# adruino_robot_rev.net
KiCad netlist of a schematic drawn in EAGLE
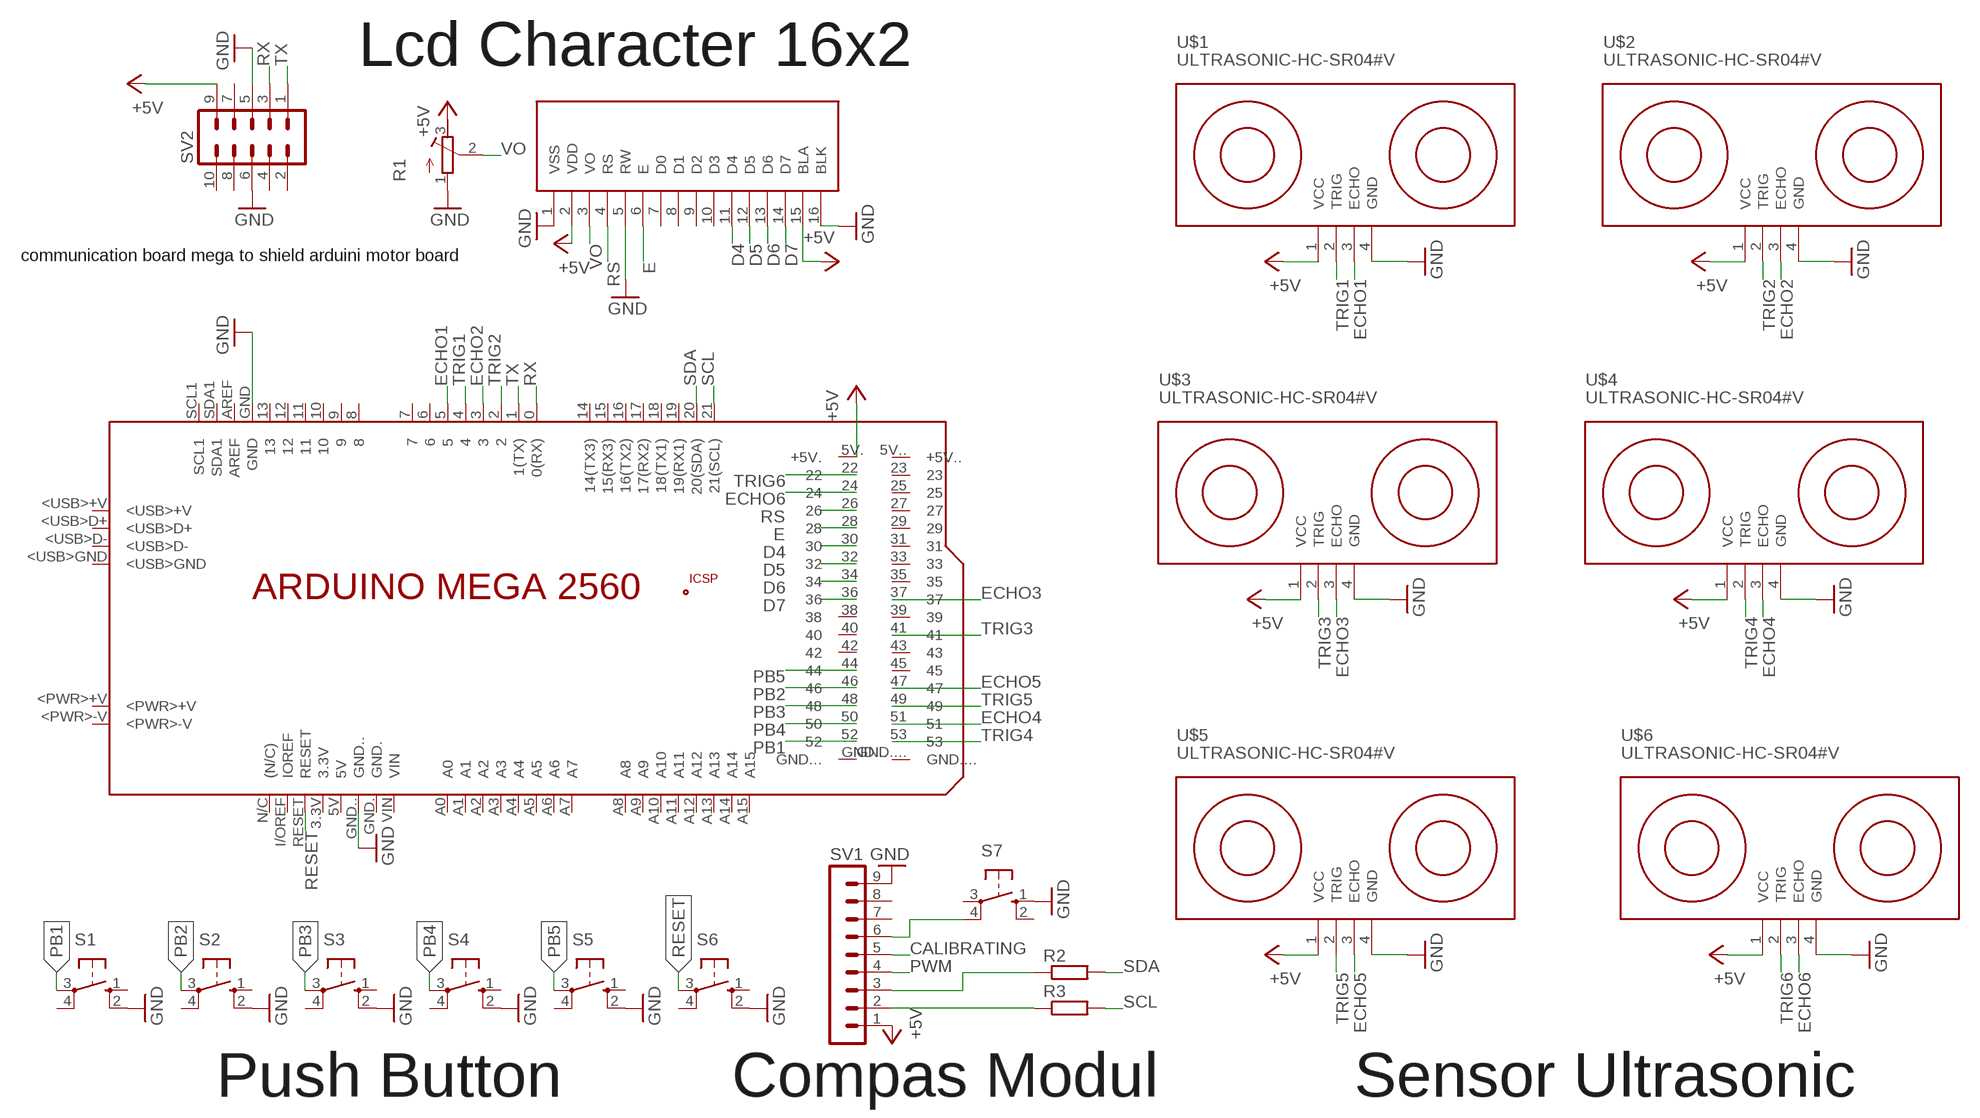
[diagram p0: schematic, sheet 1]

(export (version "E")
  (design (tool "Eeschema 10.0.6"))
  (components
    (comp (ref "PCB1")
      (value "ARDUINO_MEGA2560")
      (footprint "eagle-import:ARDUINO_MEGA2560")
      (libsource (lib "eagle-import") (part "ARDUINO_MEGA2560"))
    )
    (comp (ref "R1")
      (value "R-TRIMM3339P")
      (footprint "eagle-import:RTRIM3339P")
      (libsource (lib "eagle-import") (part "R-TRIMM3339P"))
    )
    (comp (ref "R2")
      (value "R-EU_0204/7")
      (footprint "eagle-import:0204_7")
      (libsource (lib "eagle-import") (part "R-EU_0204/7"))
    )
    (comp (ref "R3")
      (value "R-EU_0204/7")
      (footprint "eagle-import:0204_7")
      (libsource (lib "eagle-import") (part "R-EU_0204/7"))
    )
    (comp (ref "S1")
      (value "40-XX")
      (footprint "eagle-import:B3F-40XX")
      (fields (field (name "MF") "OMRON COMPONENTS USA") (field (name "MPN") "B3F-4000"))
      (libsource (lib "eagle-import") (part "40-XX"))
    )
    (comp (ref "S2")
      (value "40-XX")
      (footprint "eagle-import:B3F-40XX")
      (fields (field (name "MF") "OMRON COMPONENTS USA") (field (name "MPN") "B3F-4000"))
      (libsource (lib "eagle-import") (part "40-XX"))
    )
    (comp (ref "S3")
      (value "40-XX")
      (footprint "eagle-import:B3F-40XX")
      (fields (field (name "MF") "OMRON COMPONENTS USA") (field (name "MPN") "B3F-4000"))
      (libsource (lib "eagle-import") (part "40-XX"))
    )
    (comp (ref "S4")
      (value "40-XX")
      (footprint "eagle-import:B3F-40XX")
      (fields (field (name "MF") "OMRON COMPONENTS USA") (field (name "MPN") "B3F-4000"))
      (libsource (lib "eagle-import") (part "40-XX"))
    )
    (comp (ref "S5")
      (value "40-XX")
      (footprint "eagle-import:B3F-40XX")
      (fields (field (name "MF") "OMRON COMPONENTS USA") (field (name "MPN") "B3F-4000"))
      (libsource (lib "eagle-import") (part "40-XX"))
    )
    (comp (ref "S6")
      (value "40-XX")
      (footprint "eagle-import:B3F-40XX")
      (fields (field (name "MF") "OMRON COMPONENTS USA") (field (name "MPN") "B3F-4000"))
      (libsource (lib "eagle-import") (part "40-XX"))
    )
    (comp (ref "S7")
      (value "40-XX")
      (footprint "eagle-import:B3F-40XX")
      (fields (field (name "MF") "OMRON COMPONENTS USA") (field (name "MPN") "B3F-4000"))
      (libsource (lib "eagle-import") (part "40-XX"))
    )
    (comp (ref "SV1")
      (value "MA09-1")
      (footprint "eagle-import:MA09-1")
      (libsource (lib "eagle-import") (part "MA09-1"))
    )
    (comp (ref "SV2")
      (value "ML10")
      (footprint "eagle-import:ML10")
      (libsource (lib "eagle-import") (part "ML10"))
    )
    (comp (ref "U$1")
      (value "ULTRASONIC-HC-SR04#V")
      (footprint "eagle-import:ULTRASONIC-HC-SR04#V")
      (libsource (lib "eagle-import") (part "ULTRASONIC-HC-SR04#V"))
    )
    (comp (ref "U$2")
      (value "ULTRASONIC-HC-SR04#V")
      (footprint "eagle-import:ULTRASONIC-HC-SR04#V")
      (libsource (lib "eagle-import") (part "ULTRASONIC-HC-SR04#V"))
    )
    (comp (ref "U$3")
      (value "ULTRASONIC-HC-SR04#V")
      (footprint "eagle-import:ULTRASONIC-HC-SR04#V")
      (libsource (lib "eagle-import") (part "ULTRASONIC-HC-SR04#V"))
    )
    (comp (ref "U$4")
      (value "ULTRASONIC-HC-SR04#V")
      (footprint "eagle-import:ULTRASONIC-HC-SR04#V")
      (libsource (lib "eagle-import") (part "ULTRASONIC-HC-SR04#V"))
    )
    (comp (ref "U$5")
      (value "ULTRASONIC-HC-SR04#V")
      (footprint "eagle-import:ULTRASONIC-HC-SR04#V")
      (libsource (lib "eagle-import") (part "ULTRASONIC-HC-SR04#V"))
    )
    (comp (ref "U$6")
      (value "ULTRASONIC-HC-SR04#V")
      (footprint "eagle-import:ULTRASONIC-HC-SR04#V")
      (libsource (lib "eagle-import") (part "ULTRASONIC-HC-SR04#V"))
    )
    (comp (ref "U$7")
      (value "2X16LCDTOP")
      (footprint "eagle-import:2X16LCDTOP")
      (libsource (lib "eagle-import") (part "2X16LCDTOP"))
    )
  )
  (nets
    (net (code "1") (name "+5V") (class "Default")
      (node (ref "PCB1") (pin "5V.") (pinfunction "+5V._5V.") (pintype "bidirectional"))
      (node (ref "R1") (pin "3") (pinfunction "E_3") (pintype "passive"))
      (node (ref "SV1") (pin "1") (pinfunction "1_1") (pintype "passive"))
      (node (ref "SV2") (pin "9") (pinfunction "9_9") (pintype "passive"))
      (node (ref "U$1") (pin "1") (pinfunction "VCC_1") (pintype "power_in"))
      (node (ref "U$2") (pin "1") (pinfunction "VCC_1") (pintype "power_in"))
      (node (ref "U$3") (pin "1") (pinfunction "VCC_1") (pintype "power_in"))
      (node (ref "U$4") (pin "1") (pinfunction "VCC_1") (pintype "power_in"))
      (node (ref "U$5") (pin "1") (pinfunction "VCC_1") (pintype "power_in"))
      (node (ref "U$6") (pin "1") (pinfunction "VCC_1") (pintype "power_in"))
      (node (ref "U$7") (pin "15") (pinfunction "BLA_15") (pintype "bidirectional"))
      (node (ref "U$7") (pin "2") (pinfunction "VDD_2") (pintype "bidirectional"))
    )
    (net (code "2") (name "/CALIBRATING") (class "Default")
      (node (ref "SV1") (pin "5") (pinfunction "5_5") (pintype "passive"))
    )
    (net (code "3") (name "/D4") (class "Default")
      (node (ref "PCB1") (pin "30") (pinfunction "30_30") (pintype "bidirectional"))
      (node (ref "U$7") (pin "11") (pinfunction "D4_11") (pintype "bidirectional"))
    )
    (net (code "4") (name "/D5") (class "Default")
      (node (ref "PCB1") (pin "32") (pinfunction "32_32") (pintype "bidirectional"))
      (node (ref "U$7") (pin "12") (pinfunction "D5_12") (pintype "bidirectional"))
    )
    (net (code "5") (name "/D6") (class "Default")
      (node (ref "PCB1") (pin "34") (pinfunction "34_34") (pintype "bidirectional"))
      (node (ref "U$7") (pin "13") (pinfunction "D6_13") (pintype "bidirectional"))
    )
    (net (code "6") (name "/D7") (class "Default")
      (node (ref "PCB1") (pin "36") (pinfunction "36_36") (pintype "bidirectional"))
      (node (ref "U$7") (pin "14") (pinfunction "D7_14") (pintype "bidirectional"))
    )
    (net (code "7") (name "/E") (class "Default")
      (node (ref "PCB1") (pin "28") (pinfunction "28_28") (pintype "bidirectional"))
      (node (ref "U$7") (pin "6") (pinfunction "E_6") (pintype "bidirectional"))
    )
    (net (code "8") (name "/ECHO1") (class "Default")
      (node (ref "PCB1") (pin "5") (pinfunction "5_5") (pintype "bidirectional"))
      (node (ref "U$1") (pin "3") (pinfunction "ECHO_3") (pintype "output"))
    )
    (net (code "9") (name "/ECHO2") (class "Default")
      (node (ref "PCB1") (pin "3") (pinfunction "3_3") (pintype "bidirectional"))
      (node (ref "U$2") (pin "3") (pinfunction "ECHO_3") (pintype "output"))
    )
    (net (code "10") (name "/ECHO3") (class "Default")
      (node (ref "PCB1") (pin "37") (pinfunction "37_37") (pintype "bidirectional"))
      (node (ref "U$3") (pin "3") (pinfunction "ECHO_3") (pintype "output"))
    )
    (net (code "11") (name "/ECHO4") (class "Default")
      (node (ref "PCB1") (pin "51") (pinfunction "51_51") (pintype "bidirectional"))
      (node (ref "U$4") (pin "3") (pinfunction "ECHO_3") (pintype "output"))
    )
    (net (code "12") (name "/ECHO5") (class "Default")
      (node (ref "PCB1") (pin "47") (pinfunction "47_47") (pintype "bidirectional"))
      (node (ref "U$5") (pin "3") (pinfunction "ECHO_3") (pintype "output"))
    )
    (net (code "13") (name "/ECHO6") (class "Default")
      (node (ref "PCB1") (pin "24") (pinfunction "24_24") (pintype "bidirectional"))
      (node (ref "U$6") (pin "3") (pinfunction "ECHO_3") (pintype "output"))
    )
    (net (code "14") (name "/PWM") (class "Default")
      (node (ref "SV1") (pin "4") (pinfunction "4_4") (pintype "passive"))
    )
    (net (code "15") (name "/RS") (class "Default")
      (node (ref "PCB1") (pin "26") (pinfunction "26_26") (pintype "bidirectional"))
      (node (ref "U$7") (pin "4") (pinfunction "RS_4") (pintype "bidirectional"))
    )
    (net (code "16") (name "/RX") (class "Default")
      (node (ref "PCB1") (pin "0") (pinfunction "0(RX)_0") (pintype "bidirectional"))
      (node (ref "SV2") (pin "3") (pinfunction "3_3") (pintype "passive"))
    )
    (net (code "17") (name "/SCL") (class "Default")
      (node (ref "PCB1") (pin "21") (pinfunction "21(SCL)_21") (pintype "bidirectional"))
      (node (ref "R3") (pin "2") (pinfunction "2_2") (pintype "passive"))
    )
    (net (code "18") (name "/SDA") (class "Default")
      (node (ref "PCB1") (pin "20") (pinfunction "20(SDA)_20") (pintype "bidirectional"))
      (node (ref "R2") (pin "2") (pinfunction "2_2") (pintype "passive"))
    )
    (net (code "19") (name "/TRIG1") (class "Default")
      (node (ref "PCB1") (pin "4") (pinfunction "4_4") (pintype "bidirectional"))
      (node (ref "U$1") (pin "2") (pinfunction "TRIG_2") (pintype "input"))
    )
    (net (code "20") (name "/TRIG2") (class "Default")
      (node (ref "PCB1") (pin "2") (pinfunction "2_2") (pintype "bidirectional"))
      (node (ref "U$2") (pin "2") (pinfunction "TRIG_2") (pintype "input"))
    )
    (net (code "21") (name "/TRIG3") (class "Default")
      (node (ref "PCB1") (pin "41") (pinfunction "41_41") (pintype "bidirectional"))
      (node (ref "U$3") (pin "2") (pinfunction "TRIG_2") (pintype "input"))
    )
    (net (code "22") (name "/TRIG4") (class "Default")
      (node (ref "PCB1") (pin "53") (pinfunction "53_53") (pintype "bidirectional"))
      (node (ref "U$4") (pin "2") (pinfunction "TRIG_2") (pintype "input"))
    )
    (net (code "23") (name "/TRIG5") (class "Default")
      (node (ref "PCB1") (pin "49") (pinfunction "49_49") (pintype "bidirectional"))
      (node (ref "U$5") (pin "2") (pinfunction "TRIG_2") (pintype "input"))
    )
    (net (code "24") (name "/TRIG6") (class "Default")
      (node (ref "PCB1") (pin "22") (pinfunction "22_22") (pintype "bidirectional"))
      (node (ref "U$6") (pin "2") (pinfunction "TRIG_2") (pintype "input"))
    )
    (net (code "25") (name "/TX") (class "Default")
      (node (ref "PCB1") (pin "1") (pinfunction "1(TX)_1") (pintype "bidirectional"))
      (node (ref "SV2") (pin "1") (pinfunction "1_1") (pintype "passive"))
    )
    (net (code "26") (name "/VO") (class "Default")
      (node (ref "R1") (pin "2") (pinfunction "S_2") (pintype "passive"))
      (node (ref "U$7") (pin "3") (pinfunction "VO_3") (pintype "bidirectional"))
    )
    (net (code "27") (name "GND") (class "Default")
      (node (ref "PCB1") (pin "GND") (pinfunction "GND_GND") (pintype "bidirectional"))
      (node (ref "PCB1") (pin "GND..") (pinfunction "GND.._GND..") (pintype "bidirectional"))
      (node (ref "R1") (pin "1") (pinfunction "A_1") (pintype "passive"))
      (node (ref "S1") (pin "2") (pinfunction "S1_2") (pintype "passive"))
      (node (ref "S2") (pin "2") (pinfunction "S1_2") (pintype "passive"))
      (node (ref "S3") (pin "2") (pinfunction "S1_2") (pintype "passive"))
      (node (ref "S4") (pin "2") (pinfunction "S1_2") (pintype "passive"))
      (node (ref "S5") (pin "2") (pinfunction "S1_2") (pintype "passive"))
      (node (ref "S6") (pin "2") (pinfunction "S1_2") (pintype "passive"))
      (node (ref "S7") (pin "1") (pinfunction "S_1") (pintype "passive"))
      (node (ref "SV1") (pin "9") (pinfunction "9_9") (pintype "passive"))
      (node (ref "SV2") (pin "5") (pinfunction "5_5") (pintype "passive"))
      (node (ref "SV2") (pin "6") (pinfunction "6_6") (pintype "passive"))
      (node (ref "U$1") (pin "4") (pinfunction "GND_4") (pintype "power_in"))
      (node (ref "U$2") (pin "4") (pinfunction "GND_4") (pintype "power_in"))
      (node (ref "U$3") (pin "4") (pinfunction "GND_4") (pintype "power_in"))
      (node (ref "U$4") (pin "4") (pinfunction "GND_4") (pintype "power_in"))
      (node (ref "U$5") (pin "4") (pinfunction "GND_4") (pintype "power_in"))
      (node (ref "U$6") (pin "4") (pinfunction "GND_4") (pintype "power_in"))
      (node (ref "U$7") (pin "1") (pinfunction "VSS_1") (pintype "bidirectional"))
      (node (ref "U$7") (pin "16") (pinfunction "BLK_16") (pintype "bidirectional"))
      (node (ref "U$7") (pin "5") (pinfunction "RW_5") (pintype "bidirectional"))
    )
    (net (code "28") (name "Net-(R2-Pad1)") (class "Default")
      (node (ref "R2") (pin "1") (pinfunction "1_1") (pintype "passive"))
      (node (ref "SV1") (pin "3") (pinfunction "3_3") (pintype "passive"))
    )
    (net (code "29") (name "Net-(R3-Pad1)") (class "Default")
      (node (ref "R3") (pin "1") (pinfunction "1_1") (pintype "passive"))
      (node (ref "SV1") (pin "2") (pinfunction "2_2") (pintype "passive"))
    )
    (net (code "30") (name "Net-(S7-P1)") (class "Default")
      (node (ref "S7") (pin "4") (pinfunction "P1_4") (pintype "passive"))
      (node (ref "SV1") (pin "6") (pinfunction "6_6") (pintype "passive"))
    )
    (net (code "31") (name "PB1") (class "Default")
      (node (ref "PCB1") (pin "52") (pinfunction "52_52") (pintype "bidirectional"))
      (node (ref "S1") (pin "3") (pinfunction "P_3") (pintype "passive"))
    )
    (net (code "32") (name "PB2") (class "Default")
      (node (ref "PCB1") (pin "46") (pinfunction "46_46") (pintype "bidirectional"))
      (node (ref "S2") (pin "3") (pinfunction "P_3") (pintype "passive"))
    )
    (net (code "33") (name "PB3") (class "Default")
      (node (ref "PCB1") (pin "48") (pinfunction "48_48") (pintype "bidirectional"))
      (node (ref "S3") (pin "3") (pinfunction "P_3") (pintype "passive"))
    )
    (net (code "34") (name "PB4") (class "Default")
      (node (ref "PCB1") (pin "50") (pinfunction "50_50") (pintype "bidirectional"))
      (node (ref "S4") (pin "3") (pinfunction "P_3") (pintype "passive"))
    )
    (net (code "35") (name "PB5") (class "Default")
      (node (ref "PCB1") (pin "44") (pinfunction "44_44") (pintype "bidirectional"))
      (node (ref "S5") (pin "3") (pinfunction "P_3") (pintype "passive"))
    )
    (net (code "36") (name "RESET") (class "Default")
      (node (ref "PCB1") (pin "RESET") (pinfunction "RESET_RESET") (pintype "bidirectional"))
      (node (ref "S6") (pin "3") (pinfunction "P_3") (pintype "passive"))
    )
    (net (code "37") (name "unconnected-(PCB1-(N{slash}C)-PadN{slash}C)") (class "Default")
      (node (ref "PCB1") (pin "N/C") (pinfunction "(N/C)_N/C") (pintype "bidirectional"))
    )
    (net (code "38") (name "unconnected-(PCB1-+5V..-Pad5V..)") (class "Default")
      (node (ref "PCB1") (pin "5V..") (pinfunction "+5V.._5V..") (pintype "bidirectional"))
    )
    (net (code "39") (name "unconnected-(PCB1-14(TX3)-Pad14)") (class "Default")
      (node (ref "PCB1") (pin "14") (pinfunction "14(TX3)_14") (pintype "bidirectional"))
    )
    (net (code "40") (name "unconnected-(PCB1-15(RX3)-Pad15)") (class "Default")
      (node (ref "PCB1") (pin "15") (pinfunction "15(RX3)_15") (pintype "bidirectional"))
    )
    (net (code "41") (name "unconnected-(PCB1-16(TX2)-Pad16)") (class "Default")
      (node (ref "PCB1") (pin "16") (pinfunction "16(TX2)_16") (pintype "bidirectional"))
    )
    (net (code "42") (name "unconnected-(PCB1-17(RX2)-Pad17)") (class "Default")
      (node (ref "PCB1") (pin "17") (pinfunction "17(RX2)_17") (pintype "bidirectional"))
    )
    (net (code "43") (name "unconnected-(PCB1-18(TX1)-Pad18)") (class "Default")
      (node (ref "PCB1") (pin "18") (pinfunction "18(TX1)_18") (pintype "bidirectional"))
    )
    (net (code "44") (name "unconnected-(PCB1-19(RX1)-Pad19)") (class "Default")
      (node (ref "PCB1") (pin "19") (pinfunction "19(RX1)_19") (pintype "bidirectional"))
    )
    (net (code "45") (name "unconnected-(PCB1-IOREF-PadI{slash}OREF)") (class "Default")
      (node (ref "PCB1") (pin "I/OREF") (pinfunction "IOREF_I/OREF") (pintype "bidirectional"))
    )
    (net (code "46") (name "unconnected-(PCB1-Pad+5V_)") (class "Default")
      (node (ref "PCB1") (pin "+5V_") (pinfunction "+5V__+5V_") (pintype "bidirectional"))
    )
    (net (code "47") (name "unconnected-(PCB1-Pad3.3V)") (class "Default")
      (node (ref "PCB1") (pin "3.3V") (pinfunction "3.3V_3.3V") (pintype "bidirectional"))
    )
    (net (code "48") (name "unconnected-(PCB1-Pad5V)") (class "Default")
      (node (ref "PCB1") (pin "5V") (pinfunction "5V_5V") (pintype "bidirectional"))
    )
    (net (code "49") (name "unconnected-(PCB1-Pad6)") (class "Default")
      (node (ref "PCB1") (pin "6") (pinfunction "6_6") (pintype "bidirectional"))
    )
    (net (code "50") (name "unconnected-(PCB1-Pad7)") (class "Default")
      (node (ref "PCB1") (pin "7") (pinfunction "7_7") (pintype "bidirectional"))
    )
    (net (code "51") (name "unconnected-(PCB1-Pad8)") (class "Default")
      (node (ref "PCB1") (pin "8") (pinfunction "8_8") (pintype "bidirectional"))
    )
    (net (code "52") (name "unconnected-(PCB1-Pad9)") (class "Default")
      (node (ref "PCB1") (pin "9") (pinfunction "9_9") (pintype "bidirectional"))
    )
    (net (code "53") (name "unconnected-(PCB1-Pad10)") (class "Default")
      (node (ref "PCB1") (pin "10") (pinfunction "10_10") (pintype "bidirectional"))
    )
    (net (code "54") (name "unconnected-(PCB1-Pad11)") (class "Default")
      (node (ref "PCB1") (pin "11") (pinfunction "11_11") (pintype "bidirectional"))
    )
    (net (code "55") (name "unconnected-(PCB1-Pad12)") (class "Default")
      (node (ref "PCB1") (pin "12") (pinfunction "12_12") (pintype "bidirectional"))
    )
    (net (code "56") (name "unconnected-(PCB1-Pad13)") (class "Default")
      (node (ref "PCB1") (pin "13") (pinfunction "13_13") (pintype "bidirectional"))
    )
    (net (code "57") (name "unconnected-(PCB1-Pad23)") (class "Default")
      (node (ref "PCB1") (pin "23") (pinfunction "23_23") (pintype "bidirectional"))
    )
    (net (code "58") (name "unconnected-(PCB1-Pad25)") (class "Default")
      (node (ref "PCB1") (pin "25") (pinfunction "25_25") (pintype "bidirectional"))
    )
    (net (code "59") (name "unconnected-(PCB1-Pad27)") (class "Default")
      (node (ref "PCB1") (pin "27") (pinfunction "27_27") (pintype "bidirectional"))
    )
    (net (code "60") (name "unconnected-(PCB1-Pad29)") (class "Default")
      (node (ref "PCB1") (pin "29") (pinfunction "29_29") (pintype "bidirectional"))
    )
    (net (code "61") (name "unconnected-(PCB1-Pad31)") (class "Default")
      (node (ref "PCB1") (pin "31") (pinfunction "31_31") (pintype "bidirectional"))
    )
    (net (code "62") (name "unconnected-(PCB1-Pad33)") (class "Default")
      (node (ref "PCB1") (pin "33") (pinfunction "33_33") (pintype "bidirectional"))
    )
    (net (code "63") (name "unconnected-(PCB1-Pad35)") (class "Default")
      (node (ref "PCB1") (pin "35") (pinfunction "35_35") (pintype "bidirectional"))
    )
    (net (code "64") (name "unconnected-(PCB1-Pad38)") (class "Default")
      (node (ref "PCB1") (pin "38") (pinfunction "38_38") (pintype "bidirectional"))
    )
    (net (code "65") (name "unconnected-(PCB1-Pad39)") (class "Default")
      (node (ref "PCB1") (pin "39") (pinfunction "39_39") (pintype "bidirectional"))
    )
    (net (code "66") (name "unconnected-(PCB1-Pad40)") (class "Default")
      (node (ref "PCB1") (pin "40") (pinfunction "40_40") (pintype "bidirectional"))
    )
    (net (code "67") (name "unconnected-(PCB1-Pad42)") (class "Default")
      (node (ref "PCB1") (pin "42") (pinfunction "42_42") (pintype "bidirectional"))
    )
    (net (code "68") (name "unconnected-(PCB1-Pad43)") (class "Default")
      (node (ref "PCB1") (pin "43") (pinfunction "43_43") (pintype "bidirectional"))
    )
    (net (code "69") (name "unconnected-(PCB1-Pad45)") (class "Default")
      (node (ref "PCB1") (pin "45") (pinfunction "45_45") (pintype "bidirectional"))
    )
    (net (code "70") (name "unconnected-(PCB1-Pad<PWR>+V)") (class "Default")
      (node (ref "PCB1") (pin "<PWR>+V") (pinfunction "<PWR>+V_<PWR>+V") (pintype "no_connect"))
    )
    (net (code "71") (name "unconnected-(PCB1-Pad<PWR>-V)") (class "Default")
      (node (ref "PCB1") (pin "<PWR>-V") (pinfunction "<PWR>-V_<PWR>-V") (pintype "no_connect"))
    )
    (net (code "72") (name "unconnected-(PCB1-Pad<USB>+V)") (class "Default")
      (node (ref "PCB1") (pin "<USB>+V") (pinfunction "<USB>+V_<USB>+V") (pintype "no_connect"))
    )
    (net (code "73") (name "unconnected-(PCB1-Pad<USB>D+)") (class "Default")
      (node (ref "PCB1") (pin "<USB>D+") (pinfunction "<USB>D+_<USB>D+") (pintype "no_connect"))
    )
    (net (code "74") (name "unconnected-(PCB1-Pad<USB>D-)") (class "Default")
      (node (ref "PCB1") (pin "<USB>D-") (pinfunction "<USB>D-_<USB>D-") (pintype "no_connect"))
    )
    (net (code "75") (name "unconnected-(PCB1-Pad<USB>GND)") (class "Default")
      (node (ref "PCB1") (pin "<USB>GND") (pinfunction "<USB>GND_<USB>GND") (pintype "no_connect"))
    )
    (net (code "76") (name "unconnected-(PCB1-PadA0)") (class "Default")
      (node (ref "PCB1") (pin "A0") (pinfunction "A0_A0") (pintype "bidirectional"))
    )
    (net (code "77") (name "unconnected-(PCB1-PadA1)") (class "Default")
      (node (ref "PCB1") (pin "A1") (pinfunction "A1_A1") (pintype "bidirectional"))
    )
    (net (code "78") (name "unconnected-(PCB1-PadA2)") (class "Default")
      (node (ref "PCB1") (pin "A2") (pinfunction "A2_A2") (pintype "bidirectional"))
    )
    (net (code "79") (name "unconnected-(PCB1-PadA3)") (class "Default")
      (node (ref "PCB1") (pin "A3") (pinfunction "A3_A3") (pintype "bidirectional"))
    )
    (net (code "80") (name "unconnected-(PCB1-PadA4)") (class "Default")
      (node (ref "PCB1") (pin "A4") (pinfunction "A4_A4") (pintype "bidirectional"))
    )
    (net (code "81") (name "unconnected-(PCB1-PadA5)") (class "Default")
      (node (ref "PCB1") (pin "A5") (pinfunction "A5_A5") (pintype "bidirectional"))
    )
    (net (code "82") (name "unconnected-(PCB1-PadA6)") (class "Default")
      (node (ref "PCB1") (pin "A6") (pinfunction "A6_A6") (pintype "bidirectional"))
    )
    (net (code "83") (name "unconnected-(PCB1-PadA7)") (class "Default")
      (node (ref "PCB1") (pin "A7") (pinfunction "A7_A7") (pintype "bidirectional"))
    )
    (net (code "84") (name "unconnected-(PCB1-PadA8)") (class "Default")
      (node (ref "PCB1") (pin "A8") (pinfunction "A8_A8") (pintype "bidirectional"))
    )
    (net (code "85") (name "unconnected-(PCB1-PadA9)") (class "Default")
      (node (ref "PCB1") (pin "A9") (pinfunction "A9_A9") (pintype "bidirectional"))
    )
    (net (code "86") (name "unconnected-(PCB1-PadA10)") (class "Default")
      (node (ref "PCB1") (pin "A10") (pinfunction "A10_A10") (pintype "bidirectional"))
    )
    (net (code "87") (name "unconnected-(PCB1-PadA11)") (class "Default")
      (node (ref "PCB1") (pin "A11") (pinfunction "A11_A11") (pintype "bidirectional"))
    )
    (net (code "88") (name "unconnected-(PCB1-PadA12)") (class "Default")
      (node (ref "PCB1") (pin "A12") (pinfunction "A12_A12") (pintype "bidirectional"))
    )
    (net (code "89") (name "unconnected-(PCB1-PadA13)") (class "Default")
      (node (ref "PCB1") (pin "A13") (pinfunction "A13_A13") (pintype "bidirectional"))
    )
    (net (code "90") (name "unconnected-(PCB1-PadA14)") (class "Default")
      (node (ref "PCB1") (pin "A14") (pinfunction "A14_A14") (pintype "bidirectional"))
    )
    (net (code "91") (name "unconnected-(PCB1-PadA15)") (class "Default")
      (node (ref "PCB1") (pin "A15") (pinfunction "A15_A15") (pintype "bidirectional"))
    )
    (net (code "92") (name "unconnected-(PCB1-PadAREF)") (class "Default")
      (node (ref "PCB1") (pin "AREF") (pinfunction "AREF_AREF") (pintype "bidirectional"))
    )
    (net (code "93") (name "unconnected-(PCB1-PadGND.)") (class "Default")
      (node (ref "PCB1") (pin "GND.") (pinfunction "GND._GND.") (pintype "bidirectional"))
    )
    (net (code "94") (name "unconnected-(PCB1-PadGND...)") (class "Default")
      (node (ref "PCB1") (pin "GND...") (pinfunction "GND..._GND...") (pintype "bidirectional"))
    )
    (net (code "95") (name "unconnected-(PCB1-PadGND....)") (class "Default")
      (node (ref "PCB1") (pin "GND....") (pinfunction "GND...._GND....") (pintype "bidirectional"))
    )
    (net (code "96") (name "unconnected-(PCB1-PadGND__)") (class "Default")
      (node (ref "PCB1") (pin "GND__") (pinfunction "GND___GND__") (pintype "bidirectional"))
    )
    (net (code "97") (name "unconnected-(PCB1-PadMISO)") (class "Default")
      (node (ref "PCB1") (pin "MISO") (pinfunction "MISO_MISO") (pintype "bidirectional"))
    )
    (net (code "98") (name "unconnected-(PCB1-PadMOSI)") (class "Default")
      (node (ref "PCB1") (pin "MOSI") (pinfunction "MOSI_MOSI") (pintype "bidirectional"))
    )
    (net (code "99") (name "unconnected-(PCB1-PadRESET.)") (class "Default")
      (node (ref "PCB1") (pin "RESET.") (pinfunction "RESET._RESET.") (pintype "bidirectional"))
    )
    (net (code "100") (name "unconnected-(PCB1-PadSCK)") (class "Default")
      (node (ref "PCB1") (pin "SCK") (pinfunction "SCK_SCK") (pintype "bidirectional"))
    )
    (net (code "101") (name "unconnected-(PCB1-PadSCL1)") (class "Default")
      (node (ref "PCB1") (pin "SCL1") (pinfunction "SCL1_SCL1") (pintype "bidirectional"))
    )
    (net (code "102") (name "unconnected-(PCB1-PadSDA1)") (class "Default")
      (node (ref "PCB1") (pin "SDA1") (pinfunction "SDA1_SDA1") (pintype "bidirectional"))
    )
    (net (code "103") (name "unconnected-(PCB1-PadVIN)") (class "Default")
      (node (ref "PCB1") (pin "VIN") (pinfunction "VIN_VIN") (pintype "bidirectional"))
    )
    (net (code "104") (name "unconnected-(S1-P1-Pad4)") (class "Default")
      (node (ref "S1") (pin "4") (pinfunction "P1_4") (pintype "passive"))
    )
    (net (code "105") (name "unconnected-(S1-S-Pad1)") (class "Default")
      (node (ref "S1") (pin "1") (pinfunction "S_1") (pintype "passive"))
    )
    (net (code "106") (name "unconnected-(S2-P1-Pad4)") (class "Default")
      (node (ref "S2") (pin "4") (pinfunction "P1_4") (pintype "passive"))
    )
    (net (code "107") (name "unconnected-(S2-S-Pad1)") (class "Default")
      (node (ref "S2") (pin "1") (pinfunction "S_1") (pintype "passive"))
    )
    (net (code "108") (name "unconnected-(S3-P1-Pad4)") (class "Default")
      (node (ref "S3") (pin "4") (pinfunction "P1_4") (pintype "passive"))
    )
    (net (code "109") (name "unconnected-(S3-S-Pad1)") (class "Default")
      (node (ref "S3") (pin "1") (pinfunction "S_1") (pintype "passive"))
    )
    (net (code "110") (name "unconnected-(S4-P1-Pad4)") (class "Default")
      (node (ref "S4") (pin "4") (pinfunction "P1_4") (pintype "passive"))
    )
    (net (code "111") (name "unconnected-(S4-S-Pad1)") (class "Default")
      (node (ref "S4") (pin "1") (pinfunction "S_1") (pintype "passive"))
    )
    (net (code "112") (name "unconnected-(S5-P1-Pad4)") (class "Default")
      (node (ref "S5") (pin "4") (pinfunction "P1_4") (pintype "passive"))
    )
    (net (code "113") (name "unconnected-(S5-S-Pad1)") (class "Default")
      (node (ref "S5") (pin "1") (pinfunction "S_1") (pintype "passive"))
    )
    (net (code "114") (name "unconnected-(S6-P1-Pad4)") (class "Default")
      (node (ref "S6") (pin "4") (pinfunction "P1_4") (pintype "passive"))
    )
    (net (code "115") (name "unconnected-(S6-S-Pad1)") (class "Default")
      (node (ref "S6") (pin "1") (pinfunction "S_1") (pintype "passive"))
    )
    (net (code "116") (name "unconnected-(S7-P-Pad3)") (class "Default")
      (node (ref "S7") (pin "3") (pinfunction "P_3") (pintype "passive"))
    )
    (net (code "117") (name "unconnected-(S7-S1-Pad2)") (class "Default")
      (node (ref "S7") (pin "2") (pinfunction "S1_2") (pintype "passive"))
    )
    (net (code "118") (name "unconnected-(SV1-Pad7)") (class "Default")
      (node (ref "SV1") (pin "7") (pinfunction "7_7") (pintype "passive"))
    )
    (net (code "119") (name "unconnected-(SV1-Pad8)") (class "Default")
      (node (ref "SV1") (pin "8") (pinfunction "8_8") (pintype "passive"))
    )
    (net (code "120") (name "unconnected-(SV2-Pad2)") (class "Default")
      (node (ref "SV2") (pin "2") (pinfunction "2_2") (pintype "passive"))
    )
    (net (code "121") (name "unconnected-(SV2-Pad4)") (class "Default")
      (node (ref "SV2") (pin "4") (pinfunction "4_4") (pintype "passive"))
    )
    (net (code "122") (name "unconnected-(SV2-Pad7)") (class "Default")
      (node (ref "SV2") (pin "7") (pinfunction "7_7") (pintype "passive"))
    )
    (net (code "123") (name "unconnected-(SV2-Pad8)") (class "Default")
      (node (ref "SV2") (pin "8") (pinfunction "8_8") (pintype "passive"))
    )
    (net (code "124") (name "unconnected-(SV2-Pad10)") (class "Default")
      (node (ref "SV2") (pin "10") (pinfunction "10_10") (pintype "passive"))
    )
    (net (code "125") (name "unconnected-(U$7-D0-Pad7)") (class "Default")
      (node (ref "U$7") (pin "7") (pinfunction "D0_7") (pintype "bidirectional"))
    )
    (net (code "126") (name "unconnected-(U$7-D1-Pad8)") (class "Default")
      (node (ref "U$7") (pin "8") (pinfunction "D1_8") (pintype "bidirectional"))
    )
    (net (code "127") (name "unconnected-(U$7-D2-Pad9)") (class "Default")
      (node (ref "U$7") (pin "9") (pinfunction "D2_9") (pintype "bidirectional"))
    )
    (net (code "128") (name "unconnected-(U$7-D3-Pad10)") (class "Default")
      (node (ref "U$7") (pin "10") (pinfunction "D3_10") (pintype "bidirectional"))
    )
  )
)
